# GLCD-Shield_v10.net
KiCad netlist of a schematic drawn in EAGLE
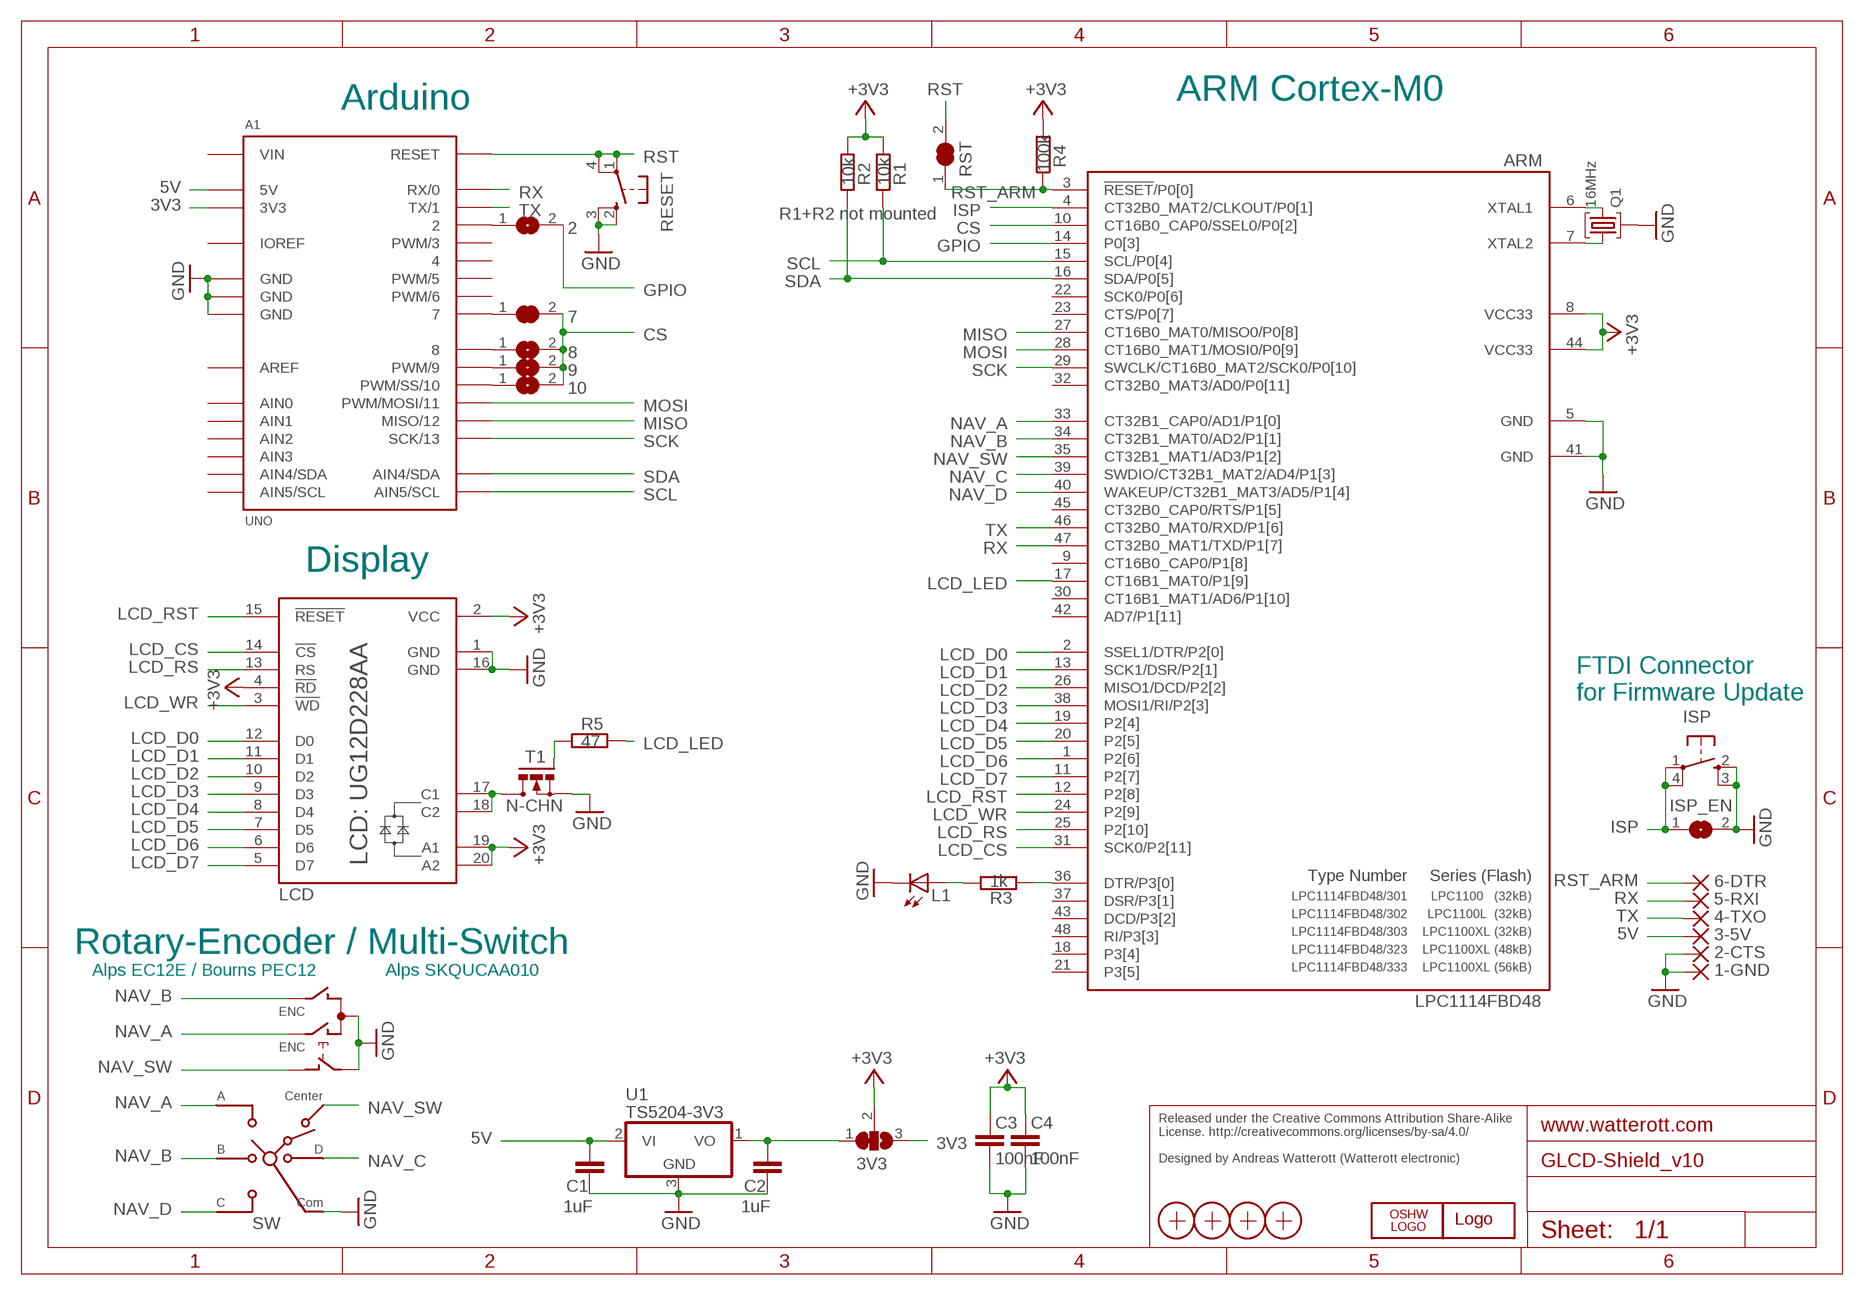
[diagram p0: schematic, sheet 1]

(export (version "E")
  (design (tool "Eeschema 10.0.6"))
  (components
    (comp (ref "1-GND")
      (value "WIREPADSMD1,27-254")
      (footprint "eagle-import:SMD1,27-2,54")
      (libsource (lib "eagle-import") (part "WIREPADSMD1,27-254"))
    )
    (comp (ref "2") (value "SJ") (footprint "eagle-import:SJ") (libsource (lib "eagle-import") (part "SJ")))
    (comp (ref "2-CTS")
      (value "WIREPADSMD1,27-254")
      (footprint "eagle-import:SMD1,27-2,54")
      (libsource (lib "eagle-import") (part "WIREPADSMD1,27-254"))
    )
    (comp (ref "3-5V")
      (value "WIREPADSMD1,27-254")
      (footprint "eagle-import:SMD1,27-2,54")
      (libsource (lib "eagle-import") (part "WIREPADSMD1,27-254"))
    )
    (comp (ref "3V3")
      (value "SJ2W")
      (footprint "eagle-import:SJ_2")
      (libsource (lib "eagle-import") (part "SJ2W"))
    )
    (comp (ref "4-TXO")
      (value "WIREPADSMD1,27-254")
      (footprint "eagle-import:SMD1,27-2,54")
      (libsource (lib "eagle-import") (part "WIREPADSMD1,27-254"))
    )
    (comp (ref "5-RXI")
      (value "WIREPADSMD1,27-254")
      (footprint "eagle-import:SMD1,27-2,54")
      (libsource (lib "eagle-import") (part "WIREPADSMD1,27-254"))
    )
    (comp (ref "6-DTR")
      (value "WIREPADSMD1,27-254")
      (footprint "eagle-import:SMD1,27-2,54")
      (libsource (lib "eagle-import") (part "WIREPADSMD1,27-254"))
    )
    (comp (ref "7") (value "SJ") (footprint "eagle-import:SJ") (libsource (lib "eagle-import") (part "SJ")))
    (comp (ref "8") (value "SJ") (footprint "eagle-import:SJ") (libsource (lib "eagle-import") (part "SJ")))
    (comp (ref "9") (value "SJ") (footprint "eagle-import:SJ") (libsource (lib "eagle-import") (part "SJ")))
    (comp (ref "10") (value "SJ") (footprint "eagle-import:SJ") (libsource (lib "eagle-import") (part "SJ")))
    (comp (ref "A1")
      (value "UNO")
      (footprint "eagle-import:UNO")
      (libsource (lib "eagle-import") (part "UNO"))
    )
    (comp (ref "ARM")
      (value "LPC1114FBD48")
      (footprint "eagle-import:LQFP48")
      (libsource (lib "eagle-import") (part "LPC111X"))
    )
    (comp (ref "C1")
      (value "1uF")
      (footprint "eagle-import:C0603")
      (libsource (lib "eagle-import") (part "C-EUC0603"))
    )
    (comp (ref "C2")
      (value "1uF")
      (footprint "eagle-import:C0603")
      (libsource (lib "eagle-import") (part "C-EUC0603"))
    )
    (comp (ref "C3")
      (value "100nF")
      (footprint "eagle-import:C0603")
      (libsource (lib "eagle-import") (part "C-EUC0603"))
    )
    (comp (ref "C4")
      (value "100nF")
      (footprint "eagle-import:C0603")
      (libsource (lib "eagle-import") (part "C-EUC0603"))
    )
    (comp (ref "ENC")
      (value "EC12E_SW")
      (footprint "eagle-import:ALPS_EC12E_SW")
      (libsource (lib "eagle-import") (part "EC12E_SW"))
    )
    (comp (ref "ISP")
      (value "SW_SMDS")
      (footprint "eagle-import:SW_SMD4@1")
      (libsource (lib "eagle-import") (part "SW_SMDS"))
    )
    (comp (ref "ISP_EN")
      (value "SJ")
      (footprint "eagle-import:SJ")
      (libsource (lib "eagle-import") (part "SJ"))
    )
    (comp (ref "L1")
      (value "LEDCHIPLED_0603")
      (footprint "eagle-import:CHIPLED_0603")
      (libsource (lib "eagle-import") (part "LEDCHIPLED_0603"))
    )
    (comp (ref "LCD")
      (value "UG12D228AA")
      (footprint "eagle-import:UG12D228AA")
      (libsource (lib "eagle-import") (part "UG12D228AA"))
    )
    (comp (ref "LOGO1")
      (value "OSHW_LOGO_6MILX0100-NT")
      (footprint "eagle-import:OSHW_6X100_NOTEXT")
      (libsource (lib "eagle-import") (part "OSHW_LOGO_6MILX0100-NT"))
    )
    (comp (ref "Q1")
      (value "16MHz")
      (footprint "eagle-import:SMD_OSC_35X15")
      (libsource (lib "eagle-import") (part "SMD_OSC2"))
    )
    (comp (ref "R1")
      (value "10k")
      (footprint "eagle-import:R0603")
      (libsource (lib "eagle-import") (part "R-EU_R0603"))
    )
    (comp (ref "R2")
      (value "10k")
      (footprint "eagle-import:R0603")
      (libsource (lib "eagle-import") (part "R-EU_R0603"))
    )
    (comp (ref "R3")
      (value "1k")
      (footprint "eagle-import:R0603")
      (libsource (lib "eagle-import") (part "R-EU_R0603"))
    )
    (comp (ref "R4")
      (value "100k")
      (footprint "eagle-import:R0603")
      (libsource (lib "eagle-import") (part "R-EU_R0603"))
    )
    (comp (ref "R5")
      (value "47")
      (footprint "eagle-import:R0603")
      (libsource (lib "eagle-import") (part "R-EU_R0603"))
    )
    (comp (ref "RESET")
      (value "SW_SMDS")
      (footprint "eagle-import:SW_SMD4@1")
      (libsource (lib "eagle-import") (part "SW_SMDS"))
    )
    (comp (ref "RST") (value "SJ") (footprint "eagle-import:SJ") (libsource (lib "eagle-import") (part "SJ")))
    (comp (ref "SW")
      (value "SKQUCAA010")
      (footprint "eagle-import:SKQU")
      (fields (field (name "MF") "ALPS"))
      (libsource (lib "eagle-import") (part "SKQUCAA010"))
    )
    (comp (ref "T1")
      (value "N-CHN")
      (footprint "eagle-import:MICRO3")
      (libsource (lib "eagle-import") (part "IRLML2502"))
    )
    (comp (ref "U$1")
      (value "WE-LOGOPLACE")
      (footprint "eagle-import:WE-LOGO")
      (libsource (lib "eagle-import") (part "WE-LOGOPLACE"))
    )
    (comp (ref "U1")
      (value "TS5204-3V3")
      (footprint "eagle-import:SOT23")
      (libsource (lib "eagle-import") (part "TS5204"))
    )
    (comp (ref "X1")
      (value "PASSER")
      (footprint "eagle-import:PASSER")
      (libsource (lib "eagle-import") (part "PASSER"))
    )
    (comp (ref "X2")
      (value "PASSER")
      (footprint "eagle-import:PASSER")
      (libsource (lib "eagle-import") (part "PASSER"))
    )
    (comp (ref "X3")
      (value "PASSER")
      (footprint "eagle-import:PASSER")
      (libsource (lib "eagle-import") (part "PASSER"))
    )
    (comp (ref "X4")
      (value "PASSER")
      (footprint "eagle-import:PASSER")
      (libsource (lib "eagle-import") (part "PASSER"))
    )
  )
  (nets
    (net (code "1") (name "+3V3") (class "Default")
      (node (ref "3V3") (pin "2") (pinfunction "2_2") (pintype "passive"))
      (node (ref "ARM") (pin "44") (pinfunction "VCC33_44") (pintype "bidirectional"))
      (node (ref "ARM") (pin "8") (pinfunction "VCC33_8") (pintype "bidirectional"))
      (node (ref "C3") (pin "1") (pinfunction "1_1") (pintype "passive"))
      (node (ref "C4") (pin "1") (pinfunction "1_1") (pintype "passive"))
      (node (ref "LCD") (pin "19") (pinfunction "A1_19") (pintype "power_in"))
      (node (ref "LCD") (pin "2") (pinfunction "VCC_2") (pintype "power_in"))
      (node (ref "LCD") (pin "20") (pinfunction "A2_20") (pintype "power_in"))
      (node (ref "LCD") (pin "4") (pinfunction "~{RD}_4") (pintype "input"))
      (node (ref "R1") (pin "2") (pinfunction "2_2") (pintype "passive"))
      (node (ref "R2") (pin "2") (pinfunction "2_2") (pintype "passive"))
      (node (ref "R4") (pin "2") (pinfunction "2_2") (pintype "passive"))
    )
    (net (code "2") (name "/3V3") (class "Default")
      (node (ref "3V3") (pin "3") (pinfunction "3_3") (pintype "passive"))
      (node (ref "A1") (pin "3V3") (pinfunction "3V3_3V3") (pintype "power_in"))
    )
    (net (code "3") (name "/5V") (class "Default")
      (node (ref "3-5V") (pin "1") (pinfunction "P_1") (pintype "passive"))
      (node (ref "A1") (pin "5V") (pinfunction "5V_5V") (pintype "power_in"))
      (node (ref "C1") (pin "1") (pinfunction "1_1") (pintype "passive"))
      (node (ref "U1") (pin "2") (pinfunction "VI_2") (pintype "input"))
    )
    (net (code "4") (name "/AREF") (class "Default")
      (node (ref "A1") (pin "AREF") (pinfunction "AREF_AREF") (pintype "power_in"))
    )
    (net (code "5") (name "/CS") (class "Default")
      (node (ref "10") (pin "2") (pinfunction "2_2") (pintype "passive"))
      (node (ref "7") (pin "2") (pinfunction "2_2") (pintype "passive"))
      (node (ref "8") (pin "2") (pinfunction "2_2") (pintype "passive"))
      (node (ref "9") (pin "2") (pinfunction "2_2") (pintype "passive"))
      (node (ref "ARM") (pin "10") (pinfunction "CT16B0_CAP0/SSEL0/P0[2]_10") (pintype "bidirectional"))
    )
    (net (code "6") (name "/GPIO") (class "Default")
      (node (ref "2") (pin "2") (pinfunction "2_2") (pintype "passive"))
      (node (ref "ARM") (pin "14") (pinfunction "P0[3]_14") (pintype "bidirectional"))
    )
    (net (code "7") (name "/IOREF") (class "Default")
      (node (ref "A1") (pin "IOREF") (pinfunction "IOREF_IOREF") (pintype "power_in"))
    )
    (net (code "8") (name "/ISP") (class "Default")
      (node (ref "ARM") (pin "4") (pinfunction "CT32B0_MAT2/CLKOUT/P0[1]_4") (pintype "bidirectional"))
      (node (ref "ISP") (pin "1") (pinfunction "P_1") (pintype "passive"))
      (node (ref "ISP") (pin "4") (pinfunction "P1_4") (pintype "passive"))
      (node (ref "ISP_EN") (pin "1") (pinfunction "1_1") (pintype "passive"))
    )
    (net (code "9") (name "/LCD_CS") (class "Default")
      (node (ref "ARM") (pin "31") (pinfunction "SCK0/P2[11]_31") (pintype "bidirectional"))
      (node (ref "LCD") (pin "14") (pinfunction "~{CS}_14") (pintype "input"))
    )
    (net (code "10") (name "/LCD_D0") (class "Default")
      (node (ref "ARM") (pin "2") (pinfunction "SSEL1/DTR/P2[0]_2") (pintype "bidirectional"))
      (node (ref "LCD") (pin "12") (pinfunction "D0_12") (pintype "input"))
    )
    (net (code "11") (name "/LCD_D1") (class "Default")
      (node (ref "ARM") (pin "13") (pinfunction "SCK1/DSR/P2[1]_13") (pintype "bidirectional"))
      (node (ref "LCD") (pin "11") (pinfunction "D1_11") (pintype "input"))
    )
    (net (code "12") (name "/LCD_D2") (class "Default")
      (node (ref "ARM") (pin "26") (pinfunction "MISO1/DCD/P2[2]_26") (pintype "bidirectional"))
      (node (ref "LCD") (pin "10") (pinfunction "D2_10") (pintype "input"))
    )
    (net (code "13") (name "/LCD_D3") (class "Default")
      (node (ref "ARM") (pin "38") (pinfunction "MOSI1/RI/P2[3]_38") (pintype "bidirectional"))
      (node (ref "LCD") (pin "9") (pinfunction "D3_9") (pintype "input"))
    )
    (net (code "14") (name "/LCD_D4") (class "Default")
      (node (ref "ARM") (pin "19") (pinfunction "P2[4]_19") (pintype "bidirectional"))
      (node (ref "LCD") (pin "8") (pinfunction "D4_8") (pintype "input"))
    )
    (net (code "15") (name "/LCD_D5") (class "Default")
      (node (ref "ARM") (pin "20") (pinfunction "P2[5]_20") (pintype "bidirectional"))
      (node (ref "LCD") (pin "7") (pinfunction "D5_7") (pintype "input"))
    )
    (net (code "16") (name "/LCD_D6") (class "Default")
      (node (ref "ARM") (pin "1") (pinfunction "P2[6]_1") (pintype "bidirectional"))
      (node (ref "LCD") (pin "6") (pinfunction "D6_6") (pintype "input"))
    )
    (net (code "17") (name "/LCD_D7") (class "Default")
      (node (ref "ARM") (pin "11") (pinfunction "P2[7]_11") (pintype "bidirectional"))
      (node (ref "LCD") (pin "5") (pinfunction "D7_5") (pintype "input"))
    )
    (net (code "18") (name "/LCD_LED") (class "Default")
      (node (ref "ARM") (pin "17") (pinfunction "CT16B1_MAT0/P1[9]_17") (pintype "bidirectional"))
      (node (ref "R5") (pin "2") (pinfunction "2_2") (pintype "passive"))
    )
    (net (code "19") (name "/LCD_RS") (class "Default")
      (node (ref "ARM") (pin "25") (pinfunction "P2[10]_25") (pintype "bidirectional"))
      (node (ref "LCD") (pin "13") (pinfunction "RS_13") (pintype "input"))
    )
    (net (code "20") (name "/LCD_RST") (class "Default")
      (node (ref "ARM") (pin "12") (pinfunction "P2[8]_12") (pintype "bidirectional"))
      (node (ref "LCD") (pin "15") (pinfunction "~{RESET}_15") (pintype "input"))
    )
    (net (code "21") (name "/LCD_WR") (class "Default")
      (node (ref "ARM") (pin "24") (pinfunction "P2[9]_24") (pintype "bidirectional"))
      (node (ref "LCD") (pin "3") (pinfunction "~{WD}_3") (pintype "input"))
    )
    (net (code "22") (name "/MISO") (class "Default")
      (node (ref "A1") (pin "12") (pinfunction "MISO/12_12") (pintype "bidirectional"))
      (node (ref "ARM") (pin "27") (pinfunction "CT16B0_MAT0/MISO0/P0[8]_27") (pintype "bidirectional"))
    )
    (net (code "23") (name "/MOSI") (class "Default")
      (node (ref "A1") (pin "11") (pinfunction "PWM/MOSI/11_11") (pintype "bidirectional"))
      (node (ref "ARM") (pin "28") (pinfunction "CT16B0_MAT1/MOSI0/P0[9]_28") (pintype "bidirectional"))
    )
    (net (code "24") (name "/NAV_A") (class "Default")
      (node (ref "ARM") (pin "33") (pinfunction "CT32B1_CAP0/AD1/P1[0]_33") (pintype "bidirectional"))
      (node (ref "ENC") (pin "A") (pinfunction "A_A") (pintype "passive"))
      (node (ref "SW") (pin "A") (pinfunction "A_A") (pintype "passive"))
    )
    (net (code "25") (name "/NAV_B") (class "Default")
      (node (ref "ARM") (pin "34") (pinfunction "CT32B1_MAT0/AD2/P1[1]_34") (pintype "bidirectional"))
      (node (ref "ENC") (pin "B") (pinfunction "B_B") (pintype "passive"))
      (node (ref "SW") (pin "B") (pinfunction "B_B") (pintype "passive"))
    )
    (net (code "26") (name "/NAV_C") (class "Default")
      (node (ref "ARM") (pin "39") (pinfunction "SWDIO/CT32B1_MAT2/AD4/P1[3]_39") (pintype "bidirectional"))
      (node (ref "SW") (pin "D") (pinfunction "D_D") (pintype "passive"))
    )
    (net (code "27") (name "/NAV_D") (class "Default")
      (node (ref "ARM") (pin "40") (pinfunction "WAKEUP/CT32B1_MAT3/AD5/P1[4]_40") (pintype "bidirectional"))
      (node (ref "SW") (pin "C") (pinfunction "C_C") (pintype "passive"))
    )
    (net (code "28") (name "/NAV_SW") (class "Default")
      (node (ref "ARM") (pin "35") (pinfunction "CT32B1_MAT1/AD3/P1[2]_35") (pintype "bidirectional"))
      (node (ref "ENC") (pin "D") (pinfunction "1_D") (pintype "passive"))
      (node (ref "SW") (pin "CENTER") (pinfunction "CENTER_CENTER") (pintype "passive"))
    )
    (net (code "29") (name "/RST") (class "Default")
      (node (ref "A1") (pin "RST") (pinfunction "RESET_RST") (pintype "bidirectional"))
      (node (ref "RESET") (pin "1") (pinfunction "P_1") (pintype "passive"))
      (node (ref "RESET") (pin "4") (pinfunction "P1_4") (pintype "passive"))
      (node (ref "RST") (pin "2") (pinfunction "2_2") (pintype "passive"))
    )
    (net (code "30") (name "/RST_ARM") (class "Default")
      (node (ref "6-DTR") (pin "1") (pinfunction "P_1") (pintype "passive"))
      (node (ref "ARM") (pin "3") (pinfunction "~{RESET}/P0[0]_3") (pintype "bidirectional"))
      (node (ref "R4") (pin "1") (pinfunction "1_1") (pintype "passive"))
      (node (ref "RST") (pin "1") (pinfunction "1_1") (pintype "passive"))
    )
    (net (code "31") (name "/RX") (class "Default")
      (node (ref "5-RXI") (pin "1") (pinfunction "P_1") (pintype "passive"))
      (node (ref "A1") (pin "0") (pinfunction "RX/0_0") (pintype "bidirectional"))
      (node (ref "ARM") (pin "47") (pinfunction "CT32B0_MAT1/TXD/P1[7]_47") (pintype "bidirectional"))
    )
    (net (code "32") (name "/SCK") (class "Default")
      (node (ref "A1") (pin "13") (pinfunction "SCK/13_13") (pintype "bidirectional"))
      (node (ref "ARM") (pin "29") (pinfunction "SWCLK/CT16B0_MAT2/SCK0/P0[10]_29") (pintype "bidirectional"))
    )
    (net (code "33") (name "/SCL") (class "Default")
      (node (ref "A1") (pin "SCL") (pinfunction "AIN5/SCL_SCL") (pintype "bidirectional"))
      (node (ref "ARM") (pin "15") (pinfunction "SCL/P0[4]_15") (pintype "bidirectional"))
      (node (ref "R1") (pin "1") (pinfunction "1_1") (pintype "passive"))
    )
    (net (code "34") (name "/SDA") (class "Default")
      (node (ref "A1") (pin "SDA") (pinfunction "AIN4/SDA_SDA") (pintype "bidirectional"))
      (node (ref "ARM") (pin "16") (pinfunction "SDA/P0[5]_16") (pintype "bidirectional"))
      (node (ref "R2") (pin "1") (pinfunction "1_1") (pintype "passive"))
    )
    (net (code "35") (name "/TX") (class "Default")
      (node (ref "4-TXO") (pin "1") (pinfunction "P_1") (pintype "passive"))
      (node (ref "A1") (pin "1") (pinfunction "TX/1_1") (pintype "bidirectional"))
      (node (ref "ARM") (pin "46") (pinfunction "CT32B0_MAT0/RXD/P1[6]_46") (pintype "bidirectional"))
    )
    (net (code "36") (name "/VIN") (class "Default")
      (node (ref "A1") (pin "VIN") (pinfunction "VIN_VIN") (pintype "power_in"))
    )
    (net (code "37") (name "GND") (class "Default")
      (node (ref "1-GND") (pin "1") (pinfunction "P_1") (pintype "passive"))
      (node (ref "2-CTS") (pin "1") (pinfunction "P_1") (pintype "passive"))
      (node (ref "A1") (pin "GND@1") (pinfunction "GND_GND@1") (pintype "power_in"))
      (node (ref "A1") (pin "GND@2") (pinfunction "GND_GND@2") (pintype "power_in"))
      (node (ref "A1") (pin "GND@3") (pinfunction "GND_GND@3") (pintype "power_in"))
      (node (ref "ARM") (pin "41") (pinfunction "GND_41") (pintype "bidirectional"))
      (node (ref "ARM") (pin "5") (pinfunction "GND_5") (pintype "bidirectional"))
      (node (ref "C1") (pin "2") (pinfunction "2_2") (pintype "passive"))
      (node (ref "C2") (pin "2") (pinfunction "2_2") (pintype "passive"))
      (node (ref "C3") (pin "2") (pinfunction "2_2") (pintype "passive"))
      (node (ref "C4") (pin "2") (pinfunction "2_2") (pintype "passive"))
      (node (ref "ENC") (pin "C") (pinfunction "C_C") (pintype "passive"))
      (node (ref "ENC") (pin "E") (pinfunction "2_E") (pintype "passive"))
      (node (ref "ISP") (pin "2") (pinfunction "S_2") (pintype "passive"))
      (node (ref "ISP") (pin "3") (pinfunction "S1_3") (pintype "passive"))
      (node (ref "ISP_EN") (pin "2") (pinfunction "2_2") (pintype "passive"))
      (node (ref "L1") (pin "C") (pinfunction "C_C") (pintype "passive"))
      (node (ref "LCD") (pin "1") (pinfunction "GND_1") (pintype "power_in"))
      (node (ref "LCD") (pin "16") (pinfunction "GND_16") (pintype "power_in"))
      (node (ref "Q1") (pin "GND") (pinfunction "GND_GND") (pintype "passive"))
      (node (ref "RESET") (pin "2") (pinfunction "S_2") (pintype "passive"))
      (node (ref "RESET") (pin "3") (pinfunction "S1_3") (pintype "passive"))
      (node (ref "SW") (pin "COMMON") (pinfunction "COMMON_COMMON") (pintype "power_in"))
      (node (ref "T1") (pin "2") (pinfunction "S_2") (pintype "passive"))
      (node (ref "U1") (pin "3") (pinfunction "GND_3") (pintype "passive"))
    )
    (net (code "38") (name "Net-(2-Pad1)") (class "Default")
      (node (ref "2") (pin "1") (pinfunction "1_1") (pintype "passive"))
      (node (ref "A1") (pin "2") (pinfunction "2_2") (pintype "bidirectional"))
    )
    (net (code "39") (name "Net-(7-Pad1)") (class "Default")
      (node (ref "7") (pin "1") (pinfunction "1_1") (pintype "passive"))
      (node (ref "A1") (pin "7") (pinfunction "7_7") (pintype "bidirectional"))
    )
    (net (code "40") (name "Net-(8-Pad1)") (class "Default")
      (node (ref "8") (pin "1") (pinfunction "1_1") (pintype "passive"))
      (node (ref "A1") (pin "8") (pinfunction "8_8") (pintype "bidirectional"))
    )
    (net (code "41") (name "Net-(A1-PWM{slash}9)") (class "Default")
      (node (ref "9") (pin "1") (pinfunction "1_1") (pintype "passive"))
      (node (ref "A1") (pin "9") (pinfunction "PWM/9_9") (pintype "bidirectional"))
    )
    (net (code "42") (name "Net-(A1-PWM{slash}SS{slash}10)") (class "Default")
      (node (ref "10") (pin "1") (pinfunction "1_1") (pintype "passive"))
      (node (ref "A1") (pin "10") (pinfunction "PWM/SS/10_10") (pintype "bidirectional"))
    )
    (net (code "43") (name "Net-(ARM-DTR{slash}P3[0])") (class "Default")
      (node (ref "ARM") (pin "36") (pinfunction "DTR/P3[0]_36") (pintype "bidirectional"))
      (node (ref "R3") (pin "1") (pinfunction "1_1") (pintype "passive"))
    )
    (net (code "44") (name "Net-(ARM-XTAL1)") (class "Default")
      (node (ref "ARM") (pin "6") (pinfunction "XTAL1_6") (pintype "bidirectional"))
      (node (ref "Q1") (pin "2") (pinfunction "2_2") (pintype "passive"))
    )
    (net (code "45") (name "Net-(ARM-XTAL2)") (class "Default")
      (node (ref "ARM") (pin "7") (pinfunction "XTAL2_7") (pintype "bidirectional"))
      (node (ref "Q1") (pin "1") (pinfunction "1_1") (pintype "passive"))
    )
    (net (code "46") (name "Net-(L1-PadA)") (class "Default")
      (node (ref "L1") (pin "A") (pinfunction "A_A") (pintype "passive"))
      (node (ref "R3") (pin "2") (pinfunction "2_2") (pintype "passive"))
    )
    (net (code "47") (name "Net-(LCD-C1)") (class "Default")
      (node (ref "LCD") (pin "17") (pinfunction "C1_17") (pintype "power_in"))
      (node (ref "LCD") (pin "18") (pinfunction "C2_18") (pintype "power_in"))
      (node (ref "T1") (pin "3") (pinfunction "D_3") (pintype "passive"))
    )
    (net (code "48") (name "Net-(T1-G)") (class "Default")
      (node (ref "R5") (pin "1") (pinfunction "1_1") (pintype "passive"))
      (node (ref "T1") (pin "1") (pinfunction "G_1") (pintype "passive"))
    )
    (net (code "49") (name "Net-(U1-VO)") (class "Default")
      (node (ref "3V3") (pin "1") (pinfunction "1_1") (pintype "passive"))
      (node (ref "C2") (pin "1") (pinfunction "1_1") (pintype "passive"))
      (node (ref "U1") (pin "1") (pinfunction "VO_1") (pintype "passive"))
    )
    (net (code "50") (name "unconnected-(A1-AIN4{slash}SDA-PadAIN4)") (class "Default")
      (node (ref "A1") (pin "AIN4") (pinfunction "AIN4/SDA_AIN4") (pintype "bidirectional"))
    )
    (net (code "51") (name "unconnected-(A1-AIN5{slash}SCL-PadAIN5)") (class "Default")
      (node (ref "A1") (pin "AIN5") (pinfunction "AIN5/SCL_AIN5") (pintype "bidirectional"))
    )
    (net (code "52") (name "unconnected-(A1-PWM{slash}3-Pad3)") (class "Default")
      (node (ref "A1") (pin "3") (pinfunction "PWM/3_3") (pintype "bidirectional"))
    )
    (net (code "53") (name "unconnected-(A1-PWM{slash}5-Pad5)") (class "Default")
      (node (ref "A1") (pin "5") (pinfunction "PWM/5_5") (pintype "bidirectional"))
    )
    (net (code "54") (name "unconnected-(A1-PWM{slash}6-Pad6)") (class "Default")
      (node (ref "A1") (pin "6") (pinfunction "PWM/6_6") (pintype "bidirectional"))
    )
    (net (code "55") (name "unconnected-(A1-Pad4)") (class "Default")
      (node (ref "A1") (pin "4") (pinfunction "4_4") (pintype "bidirectional"))
    )
    (net (code "56") (name "unconnected-(A1-PadAIN0)") (class "Default")
      (node (ref "A1") (pin "AIN0") (pinfunction "AIN0_AIN0") (pintype "bidirectional"))
    )
    (net (code "57") (name "unconnected-(A1-PadAIN1)") (class "Default")
      (node (ref "A1") (pin "AIN1") (pinfunction "AIN1_AIN1") (pintype "bidirectional"))
    )
    (net (code "58") (name "unconnected-(A1-PadAIN2)") (class "Default")
      (node (ref "A1") (pin "AIN2") (pinfunction "AIN2_AIN2") (pintype "bidirectional"))
    )
    (net (code "59") (name "unconnected-(A1-PadAIN3)") (class "Default")
      (node (ref "A1") (pin "AIN3") (pinfunction "AIN3_AIN3") (pintype "bidirectional"))
    )
    (net (code "60") (name "unconnected-(ARM-AD7{slash}P1[11]-Pad42)") (class "Default")
      (node (ref "ARM") (pin "42") (pinfunction "AD7/P1[11]_42") (pintype "bidirectional"))
    )
    (net (code "61") (name "unconnected-(ARM-CT16B0_CAP0{slash}P1[8]-Pad9)") (class "Default")
      (node (ref "ARM") (pin "9") (pinfunction "CT16B0_CAP0/P1[8]_9") (pintype "bidirectional"))
    )
    (net (code "62") (name "unconnected-(ARM-CT16B1_MAT1{slash}AD6{slash}P1[10]-Pad30)") (class "Default")
      (node (ref "ARM") (pin "30") (pinfunction "CT16B1_MAT1/AD6/P1[10]_30") (pintype "bidirectional"))
    )
    (net (code "63") (name "unconnected-(ARM-CT32B0_CAP0{slash}RTS{slash}P1[5]-Pad45)") (class "Default")
      (node (ref "ARM") (pin "45") (pinfunction "CT32B0_CAP0/RTS/P1[5]_45") (pintype "bidirectional"))
    )
    (net (code "64") (name "unconnected-(ARM-CT32B0_MAT3{slash}AD0{slash}P0[11]-Pad32)") (class "Default")
      (node (ref "ARM") (pin "32") (pinfunction "CT32B0_MAT3/AD0/P0[11]_32") (pintype "bidirectional"))
    )
    (net (code "65") (name "unconnected-(ARM-CTS{slash}P0[7]-Pad23)") (class "Default")
      (node (ref "ARM") (pin "23") (pinfunction "CTS/P0[7]_23") (pintype "bidirectional"))
    )
    (net (code "66") (name "unconnected-(ARM-DCD{slash}P3[2]-Pad43)") (class "Default")
      (node (ref "ARM") (pin "43") (pinfunction "DCD/P3[2]_43") (pintype "bidirectional"))
    )
    (net (code "67") (name "unconnected-(ARM-DSR{slash}P3[1]-Pad37)") (class "Default")
      (node (ref "ARM") (pin "37") (pinfunction "DSR/P3[1]_37") (pintype "bidirectional"))
    )
    (net (code "68") (name "unconnected-(ARM-P3[4]-Pad18)") (class "Default")
      (node (ref "ARM") (pin "18") (pinfunction "P3[4]_18") (pintype "bidirectional"))
    )
    (net (code "69") (name "unconnected-(ARM-P3[5]-Pad21)") (class "Default")
      (node (ref "ARM") (pin "21") (pinfunction "P3[5]_21") (pintype "bidirectional"))
    )
    (net (code "70") (name "unconnected-(ARM-RI{slash}P3[3]-Pad48)") (class "Default")
      (node (ref "ARM") (pin "48") (pinfunction "RI/P3[3]_48") (pintype "bidirectional"))
    )
    (net (code "71") (name "unconnected-(ARM-SCK0{slash}P0[6]-Pad22)") (class "Default")
      (node (ref "ARM") (pin "22") (pinfunction "SCK0/P0[6]_22") (pintype "bidirectional"))
    )
  )
)
